# CAN-FD_Shield.net
KiCad netlist of a schematic drawn in EAGLE
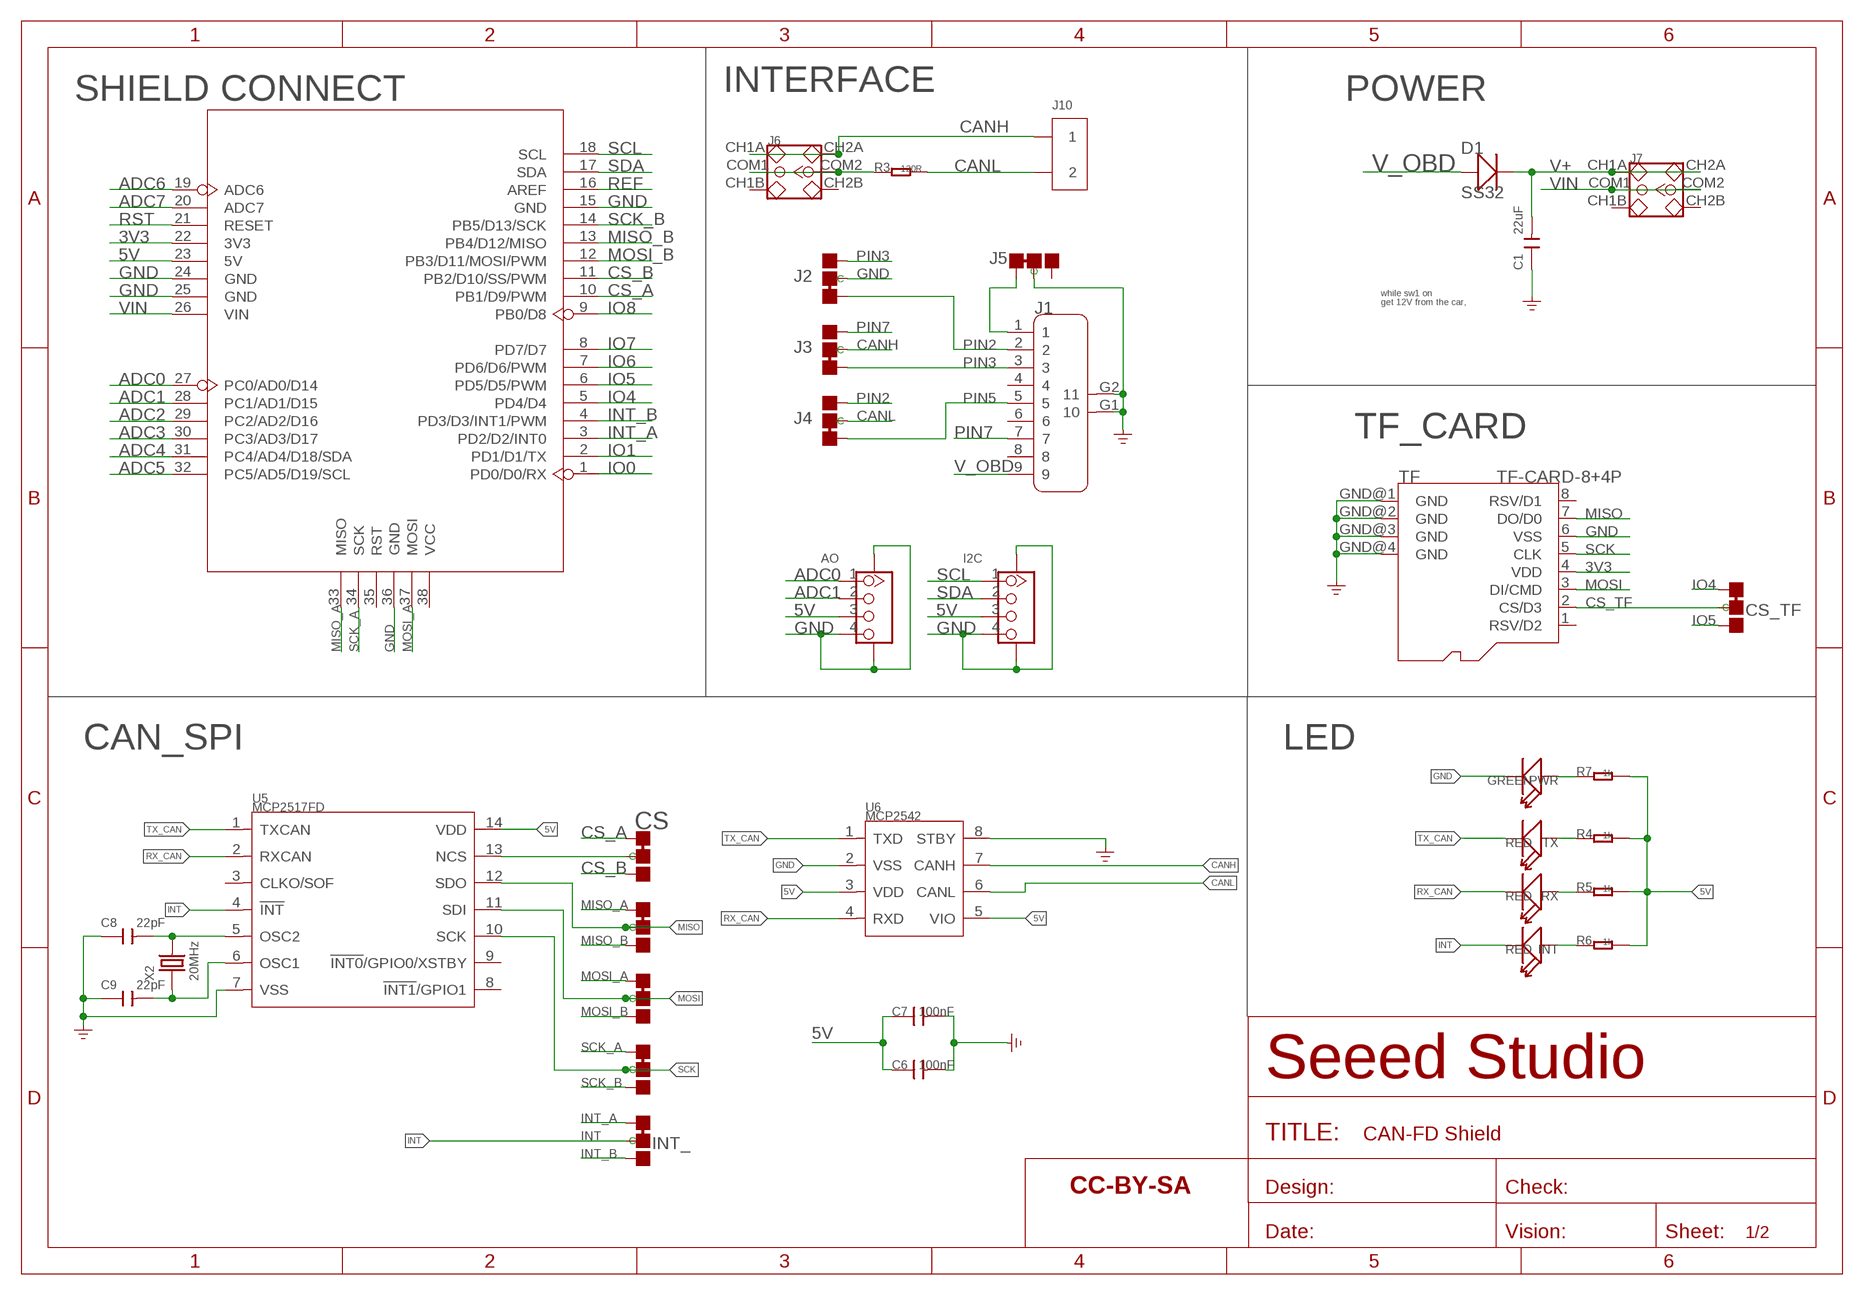
[diagram p0: schematic, sheet 1]

(export (version "E")
  (design (tool "Eeschema 10.0.6"))
  (components
    (comp (ref "AO")
      (value "GROVE-CONNECTOR-SMD'90D'")
      (footprint "eagle-import:HW4-SMD-2.0-90D")
      (libsource (lib "eagle-import") (part "GROVE-CONNECTOR-SMD'90D'"))
    )
    (comp (ref "C1")
      (value "22uF")
      (footprint "eagle-import:C1206")
      (libsource (lib "eagle-import") (part "CAP-1206"))
    )
    (comp (ref "C6")
      (value "100nF")
      (footprint "eagle-import:0603")
      (libsource (lib "eagle-import") (part "C-0603"))
    )
    (comp (ref "C7")
      (value "100nF")
      (footprint "eagle-import:0603")
      (libsource (lib "eagle-import") (part "C-0603"))
    )
    (comp (ref "C8")
      (value "22pF")
      (footprint "eagle-import:C0603")
      (libsource (lib "eagle-import") (part "CAP-0603"))
    )
    (comp (ref "C9")
      (value "22pF")
      (footprint "eagle-import:C0603")
      (libsource (lib "eagle-import") (part "CAP-0603"))
    )
    (comp (ref "CS")
      (value "JUMPER-3P-SHORT")
      (footprint "eagle-import:3P-SMD-SHORT")
      (libsource (lib "eagle-import") (part "JUMPER-3P-SHORT"))
    )
    (comp (ref "CS_TF")
      (value "JUMPER-3P-SHORT")
      (footprint "eagle-import:3P-SMD-SHORT")
      (libsource (lib "eagle-import") (part "JUMPER-3P-SHORT"))
    )
    (comp (ref "D1")
      (value "SS32")
      (footprint "eagle-import:D2010")
      (libsource (lib "eagle-import") (part "D-SMA"))
    )
    (comp (ref "I2C")
      (value "GROVE-CONNECTOR-SMD'90D'")
      (footprint "eagle-import:HW4-SMD-2.0-90D")
      (libsource (lib "eagle-import") (part "GROVE-CONNECTOR-SMD'90D'"))
    )
    (comp (ref "INT")
      (value "RED")
      (footprint "eagle-import:LED-0603")
      (libsource (lib "eagle-import") (part "LED'0603'"))
    )
    (comp (ref "INT_")
      (value "JUMPER-3P-SHORT")
      (footprint "eagle-import:3P-SMD-SHORT")
      (libsource (lib "eagle-import") (part "JUMPER-3P-SHORT"))
    )
    (comp (ref "J1")
      (value "DB9'MEAL'")
      (footprint "eagle-import:DB9-MEAL")
      (libsource (lib "eagle-import") (part "DB9'MEAL'"))
    )
    (comp (ref "J2")
      (value "JUMPER-3P-SHORT")
      (footprint "eagle-import:3P-SMD-SHORT")
      (libsource (lib "eagle-import") (part "JUMPER-3P-SHORT"))
    )
    (comp (ref "J3")
      (value "JUMPER-3P-SHORT")
      (footprint "eagle-import:3P-SMD-SHORT")
      (libsource (lib "eagle-import") (part "JUMPER-3P-SHORT"))
    )
    (comp (ref "J4")
      (value "JUMPER-3P-SHORT")
      (footprint "eagle-import:3P-SMD-SHORT")
      (libsource (lib "eagle-import") (part "JUMPER-3P-SHORT"))
    )
    (comp (ref "J5")
      (value "JUMPER-3P-SHORT")
      (footprint "eagle-import:3P-SMD-SHORT")
      (libsource (lib "eagle-import") (part "JUMPER-3P-SHORT"))
    )
    (comp (ref "J6")
      (value "SWITCH-2CH-6P")
      (footprint "eagle-import:6P-2CH-2.54-7.6X3.0")
      (libsource (lib "eagle-import") (part "SWITCH-2CH-6P"))
    )
    (comp (ref "J7")
      (value "SWITCH-2CH-6P")
      (footprint "eagle-import:6P-2CH-2.54-7.6X3.0")
      (libsource (lib "eagle-import") (part "SWITCH-2CH-6P"))
    )
    (comp (ref "J10")
      (value "SCREW-TERMINAL-2P'5.08'")
      (footprint "eagle-import:H2-5.0-10.5X8.0MM")
      (libsource (lib "eagle-import") (part "SCREW-TERMINAL-2P'5.08'"))
    )
    (comp (ref "MISO")
      (value "JUMPER-3P-SHORT")
      (footprint "eagle-import:3P-SMD-SHORT")
      (libsource (lib "eagle-import") (part "JUMPER-3P-SHORT"))
    )
    (comp (ref "MOSI")
      (value "JUMPER-3P-SHORT")
      (footprint "eagle-import:3P-SMD-SHORT")
      (libsource (lib "eagle-import") (part "JUMPER-3P-SHORT"))
    )
    (comp (ref "PWR")
      (value "GREEN")
      (footprint "eagle-import:LED-0603")
      (libsource (lib "eagle-import") (part "LED'0603'"))
    )
    (comp (ref "R3")
      (value "120R")
      (footprint "eagle-import:0603")
      (libsource (lib "eagle-import") (part "R-0603"))
    )
    (comp (ref "R4")
      (value "1k")
      (footprint "eagle-import:0603")
      (libsource (lib "eagle-import") (part "R-0603"))
    )
    (comp (ref "R5")
      (value "1k")
      (footprint "eagle-import:0603")
      (libsource (lib "eagle-import") (part "R-0603"))
    )
    (comp (ref "R6")
      (value "1k")
      (footprint "eagle-import:0603")
      (libsource (lib "eagle-import") (part "R-0603"))
    )
    (comp (ref "R7")
      (value "1k")
      (footprint "eagle-import:0603")
      (libsource (lib "eagle-import") (part "R-0603"))
    )
    (comp (ref "RX")
      (value "RED")
      (footprint "eagle-import:LED-0603")
      (libsource (lib "eagle-import") (part "LED'0603'"))
    )
    (comp (ref "SCK")
      (value "JUMPER-3P-SHORT")
      (footprint "eagle-import:3P-SMD-SHORT")
      (libsource (lib "eagle-import") (part "JUMPER-3P-SHORT"))
    )
    (comp (ref "TF")
      (value "TF-CARD-8+4P")
      (footprint "eagle-import:TF-8+4P-1.1-13.5X15MM")
      (libsource (lib "eagle-import") (part "TF-CARD-8+4P"))
    )
    (comp (ref "TX")
      (value "RED")
      (footprint "eagle-import:LED-0603")
      (libsource (lib "eagle-import") (part "LED'0603'"))
    )
    (comp (ref "U$5")
      (value "SEEEDSTUDIO-OPEN-SCH-FRAME")
      (footprint "eagle-import:SEEEDSTUDIO-PCB-FRAME")
      (libsource (lib "eagle-import") (part "SEEEDSTUDIO-OPEN-SCH-FRAME"))
    )
    (comp (ref "U4")
      (value "ARDUINO-38P'WITH/-SILK'")
      (footprint "eagle-import:ARDUINO-38P-WITH_-SILK-500519002")
      (libsource (lib "eagle-import") (part "ARDUINO-38P'WITH/-SILK'"))
    )
    (comp (ref "U5")
      (value "MCP2517FD")
      (footprint "eagle-import:SOIC14-1.27-8.6X3.9MM")
      (libsource (lib "eagle-import") (part "CONTROLLER-MCP2517FD"))
    )
    (comp (ref "U6")
      (value "MCP2542")
      (footprint "eagle-import:SOIC8-1.27-5X4MM")
      (libsource (lib "eagle-import") (part "TRANSCEIVER-MCP2542"))
    )
    (comp (ref "X2")
      (value "20MHz")
      (footprint "eagle-import:HC49US")
      (libsource (lib "eagle-import") (part "CRYSTAL-2P'HC49US'"))
    )
  )
  (nets
    (net (code "1") (name "3V3") (class "Default")
      (node (ref "TF") (pin "4") (pinfunction "VDD_4") (pintype "bidirectional"))
      (node (ref "U4") (pin "22") (pinfunction "3V3_22") (pintype "bidirectional"))
    )
    (net (code "2") (name "5V") (class "Default")
      (node (ref "AO") (pin "3") (pinfunction "3_3") (pintype "bidirectional"))
      (node (ref "C6") (pin "1") (pinfunction "1_1") (pintype "passive"))
      (node (ref "C7") (pin "1") (pinfunction "1_1") (pintype "passive"))
      (node (ref "I2C") (pin "3") (pinfunction "3_3") (pintype "bidirectional"))
      (node (ref "R4") (pin "2") (pinfunction "2_2") (pintype "passive"))
      (node (ref "R5") (pin "2") (pinfunction "2_2") (pintype "passive"))
      (node (ref "R6") (pin "2") (pinfunction "2_2") (pintype "passive"))
      (node (ref "R7") (pin "2") (pinfunction "2_2") (pintype "passive"))
      (node (ref "U4") (pin "23") (pinfunction "5V_23") (pintype "bidirectional"))
      (node (ref "U5") (pin "14") (pinfunction "VDD_14") (pintype "bidirectional"))
      (node (ref "U6") (pin "3") (pinfunction "VDD_3") (pintype "bidirectional"))
      (node (ref "U6") (pin "5") (pinfunction "VIO_5") (pintype "bidirectional"))
    )
    (net (code "3") (name "ADC0") (class "Default")
      (node (ref "AO") (pin "1") (pinfunction "1_1") (pintype "bidirectional"))
      (node (ref "U4") (pin "27") (pinfunction "PC0/AD0/D14_27") (pintype "bidirectional"))
    )
    (net (code "4") (name "ADC1") (class "Default")
      (node (ref "AO") (pin "2") (pinfunction "2_2") (pintype "bidirectional"))
      (node (ref "U4") (pin "28") (pinfunction "PC1/AD1/D15_28") (pintype "bidirectional"))
    )
    (net (code "5") (name "ADC2") (class "Default")
      (node (ref "U4") (pin "29") (pinfunction "PC2/AD2/D16_29") (pintype "bidirectional"))
    )
    (net (code "6") (name "ADC3") (class "Default")
      (node (ref "U4") (pin "30") (pinfunction "PC3/AD3/D17_30") (pintype "bidirectional"))
    )
    (net (code "7") (name "ADC4") (class "Default")
      (node (ref "U4") (pin "31") (pinfunction "PC4/AD4/D18/SDA_31") (pintype "bidirectional"))
    )
    (net (code "8") (name "ADC5") (class "Default")
      (node (ref "U4") (pin "32") (pinfunction "PC5/AD5/D19/SCL_32") (pintype "bidirectional"))
    )
    (net (code "9") (name "ADC6") (class "Default")
      (node (ref "U4") (pin "19") (pinfunction "ADC6_19") (pintype "bidirectional"))
    )
    (net (code "10") (name "ADC7") (class "Default")
      (node (ref "U4") (pin "20") (pinfunction "ADC7_20") (pintype "bidirectional"))
    )
    (net (code "11") (name "CANH") (class "Default")
      (node (ref "J10") (pin "1") (pinfunction "1_1") (pintype "bidirectional"))
      (node (ref "J3") (pin "MM") (pinfunction "C_MM") (pintype "bidirectional"))
      (node (ref "J6") (pin "CH1A") (pinfunction "CH1A_CH1A") (pintype "bidirectional"))
      (node (ref "J6") (pin "CH2A") (pinfunction "CH2A_CH2A") (pintype "bidirectional"))
      (node (ref "U6") (pin "7") (pinfunction "CANH_7") (pintype "bidirectional"))
    )
    (net (code "12") (name "CANL") (class "Default")
      (node (ref "J10") (pin "2") (pinfunction "2_2") (pintype "bidirectional"))
      (node (ref "J4") (pin "MM") (pinfunction "C_MM") (pintype "bidirectional"))
      (node (ref "R3") (pin "2") (pinfunction "2_2") (pintype "passive"))
      (node (ref "U6") (pin "6") (pinfunction "CANL_6") (pintype "bidirectional"))
    )
    (net (code "13") (name "CS_A") (class "Default")
      (node (ref "CS") (pin "11") (pinfunction "L_11") (pintype "bidirectional"))
      (node (ref "U4") (pin "10") (pinfunction "PB1/D9/PWM_10") (pintype "bidirectional"))
    )
    (net (code "14") (name "CS_B") (class "Default")
      (node (ref "CS") (pin "00") (pinfunction "R_00") (pintype "bidirectional"))
      (node (ref "U4") (pin "11") (pinfunction "PB2/D10/SS/PWM_11") (pintype "bidirectional"))
    )
    (net (code "15") (name "CS_TF") (class "Default")
      (node (ref "CS_TF") (pin "MM") (pinfunction "C_MM") (pintype "bidirectional"))
      (node (ref "TF") (pin "2") (pinfunction "CS/D3_2") (pintype "bidirectional"))
    )
    (net (code "16") (name "GND") (class "Default")
      (node (ref "AO") (pin "4") (pinfunction "4_4") (pintype "bidirectional"))
      (node (ref "AO") (pin "SS1") (pinfunction "SS1_SS1") (pintype "bidirectional"))
      (node (ref "AO") (pin "SS2") (pinfunction "SS2_SS2") (pintype "bidirectional"))
      (node (ref "C1") (pin "1") (pinfunction "1_1") (pintype "passive"))
      (node (ref "C6") (pin "2") (pinfunction "2_2") (pintype "passive"))
      (node (ref "C7") (pin "2") (pinfunction "2_2") (pintype "passive"))
      (node (ref "C8") (pin "1") (pinfunction "1_1") (pintype "passive"))
      (node (ref "C9") (pin "1") (pinfunction "1_1") (pintype "passive"))
      (node (ref "I2C") (pin "4") (pinfunction "4_4") (pintype "bidirectional"))
      (node (ref "I2C") (pin "SS1") (pinfunction "SS1_SS1") (pintype "bidirectional"))
      (node (ref "I2C") (pin "SS2") (pinfunction "SS2_SS2") (pintype "bidirectional"))
      (node (ref "J1") (pin "G1") (pinfunction "10_G1") (pintype "bidirectional"))
      (node (ref "J1") (pin "G2") (pinfunction "11_G2") (pintype "bidirectional"))
      (node (ref "J2") (pin "MM") (pinfunction "C_MM") (pintype "bidirectional"))
      (node (ref "J5") (pin "MM") (pinfunction "C_MM") (pintype "bidirectional"))
      (node (ref "PWR") (pin "-") (pinfunction "-_-") (pintype "passive"))
      (node (ref "TF") (pin "6") (pinfunction "VSS_6") (pintype "bidirectional"))
      (node (ref "TF") (pin "GND@1") (pinfunction "GND_GND@1") (pintype "bidirectional"))
      (node (ref "TF") (pin "GND@2") (pinfunction "GND_GND@2") (pintype "bidirectional"))
      (node (ref "TF") (pin "GND@3") (pinfunction "GND_GND@3") (pintype "bidirectional"))
      (node (ref "TF") (pin "GND@4") (pinfunction "GND_GND@4") (pintype "bidirectional"))
      (node (ref "U4") (pin "15") (pinfunction "GND_15") (pintype "bidirectional"))
      (node (ref "U4") (pin "24") (pinfunction "GND_24") (pintype "bidirectional"))
      (node (ref "U4") (pin "25") (pinfunction "GND_25") (pintype "bidirectional"))
      (node (ref "U4") (pin "36") (pinfunction "GND_36") (pintype "bidirectional"))
      (node (ref "U5") (pin "7") (pinfunction "VSS_7") (pintype "bidirectional"))
      (node (ref "U6") (pin "2") (pinfunction "VSS_2") (pintype "bidirectional"))
      (node (ref "U6") (pin "8") (pinfunction "STBY_8") (pintype "bidirectional"))
    )
    (net (code "17") (name "INT") (class "Default")
      (node (ref "INT") (pin "-") (pinfunction "-_-") (pintype "passive"))
      (node (ref "INT_") (pin "MM") (pinfunction "C_MM") (pintype "bidirectional"))
      (node (ref "U5") (pin "4") (pinfunction "~{INT}_4") (pintype "bidirectional"))
    )
    (net (code "18") (name "INT_A") (class "Default")
      (node (ref "INT_") (pin "11") (pinfunction "L_11") (pintype "bidirectional"))
      (node (ref "U4") (pin "3") (pinfunction "PD2/D2/INT0_3") (pintype "bidirectional"))
    )
    (net (code "19") (name "INT_B") (class "Default")
      (node (ref "INT_") (pin "00") (pinfunction "R_00") (pintype "bidirectional"))
      (node (ref "U4") (pin "4") (pinfunction "PD3/D3/INT1/PWM_4") (pintype "bidirectional"))
    )
    (net (code "20") (name "IO0") (class "Default")
      (node (ref "U4") (pin "1") (pinfunction "PD0/D0/RX_1") (pintype "bidirectional"))
    )
    (net (code "21") (name "IO1") (class "Default")
      (node (ref "U4") (pin "2") (pinfunction "PD1/D1/TX_2") (pintype "bidirectional"))
    )
    (net (code "22") (name "IO4") (class "Default")
      (node (ref "CS_TF") (pin "11") (pinfunction "L_11") (pintype "bidirectional"))
      (node (ref "U4") (pin "5") (pinfunction "PD4/D4_5") (pintype "bidirectional"))
    )
    (net (code "23") (name "IO5") (class "Default")
      (node (ref "CS_TF") (pin "00") (pinfunction "R_00") (pintype "bidirectional"))
      (node (ref "U4") (pin "6") (pinfunction "PD5/D5/PWM_6") (pintype "bidirectional"))
    )
    (net (code "24") (name "IO6") (class "Default")
      (node (ref "U4") (pin "7") (pinfunction "PD6/D6/PWM_7") (pintype "bidirectional"))
    )
    (net (code "25") (name "IO7") (class "Default")
      (node (ref "U4") (pin "8") (pinfunction "PD7/D7_8") (pintype "bidirectional"))
    )
    (net (code "26") (name "IO8") (class "Default")
      (node (ref "U4") (pin "9") (pinfunction "PB0/D8_9") (pintype "bidirectional"))
    )
    (net (code "27") (name "MISO") (class "Default")
      (node (ref "MISO") (pin "MM") (pinfunction "C_MM") (pintype "bidirectional"))
      (node (ref "TF") (pin "7") (pinfunction "DO/D0_7") (pintype "bidirectional"))
      (node (ref "U5") (pin "12") (pinfunction "SDO_12") (pintype "bidirectional"))
    )
    (net (code "28") (name "MISO_A") (class "Default")
      (node (ref "MISO") (pin "11") (pinfunction "L_11") (pintype "bidirectional"))
      (node (ref "U4") (pin "33") (pinfunction "MISO_33") (pintype "bidirectional"))
    )
    (net (code "29") (name "MISO_B") (class "Default")
      (node (ref "MISO") (pin "00") (pinfunction "R_00") (pintype "bidirectional"))
      (node (ref "U4") (pin "13") (pinfunction "PB4/D12/MISO_13") (pintype "bidirectional"))
    )
    (net (code "30") (name "MOSI") (class "Default")
      (node (ref "MOSI") (pin "MM") (pinfunction "C_MM") (pintype "bidirectional"))
      (node (ref "TF") (pin "3") (pinfunction "DI/CMD_3") (pintype "bidirectional"))
      (node (ref "U5") (pin "11") (pinfunction "SDI_11") (pintype "bidirectional"))
    )
    (net (code "31") (name "MOSI_A") (class "Default")
      (node (ref "MOSI") (pin "11") (pinfunction "L_11") (pintype "bidirectional"))
      (node (ref "U4") (pin "37") (pinfunction "MOSI_37") (pintype "bidirectional"))
    )
    (net (code "32") (name "MOSI_B") (class "Default")
      (node (ref "MOSI") (pin "00") (pinfunction "R_00") (pintype "bidirectional"))
      (node (ref "U4") (pin "12") (pinfunction "PB3/D11/MOSI/PWM_12") (pintype "bidirectional"))
    )
    (net (code "33") (name "Net-(CS-C)") (class "Default")
      (node (ref "CS") (pin "MM") (pinfunction "C_MM") (pintype "bidirectional"))
      (node (ref "U5") (pin "13") (pinfunction "NCS_13") (pintype "bidirectional"))
    )
    (net (code "34") (name "Net-(INT-Pad+)") (class "Default")
      (node (ref "INT") (pin "+") (pinfunction "+_+") (pintype "passive"))
      (node (ref "R6") (pin "1") (pinfunction "1_1") (pintype "passive"))
    )
    (net (code "35") (name "Net-(J5-L)") (class "Default")
      (node (ref "J1") (pin "1") (pinfunction "1_1") (pintype "bidirectional"))
      (node (ref "J5") (pin "11") (pinfunction "L_11") (pintype "bidirectional"))
    )
    (net (code "36") (name "Net-(J6-PadCOM1)") (class "Default")
      (node (ref "J6") (pin "COM1") (pinfunction "COM1_COM1") (pintype "bidirectional"))
      (node (ref "J6") (pin "COM2") (pinfunction "COM2_COM2") (pintype "bidirectional"))
      (node (ref "R3") (pin "1") (pinfunction "1_1") (pintype "passive"))
    )
    (net (code "37") (name "Net-(PWR-Pad+)") (class "Default")
      (node (ref "PWR") (pin "+") (pinfunction "+_+") (pintype "passive"))
      (node (ref "R7") (pin "1") (pinfunction "1_1") (pintype "passive"))
    )
    (net (code "38") (name "Net-(R4-Pad1)") (class "Default")
      (node (ref "R4") (pin "1") (pinfunction "1_1") (pintype "passive"))
      (node (ref "TX") (pin "+") (pinfunction "+_+") (pintype "passive"))
    )
    (net (code "39") (name "Net-(R5-Pad1)") (class "Default")
      (node (ref "R5") (pin "1") (pinfunction "1_1") (pintype "passive"))
      (node (ref "RX") (pin "+") (pinfunction "+_+") (pintype "passive"))
    )
    (net (code "40") (name "Net-(U5-OSC1)") (class "Default")
      (node (ref "C9") (pin "2") (pinfunction "2_2") (pintype "passive"))
      (node (ref "U5") (pin "6") (pinfunction "OSC1_6") (pintype "bidirectional"))
      (node (ref "X2") (pin "1") (pinfunction "1_1") (pintype "passive"))
    )
    (net (code "41") (name "Net-(U5-OSC2)") (class "Default")
      (node (ref "C8") (pin "2") (pinfunction "2_2") (pintype "passive"))
      (node (ref "U5") (pin "5") (pinfunction "OSC2_5") (pintype "bidirectional"))
      (node (ref "X2") (pin "2") (pinfunction "2_2") (pintype "passive"))
    )
    (net (code "42") (name "PIN2") (class "Default")
      (node (ref "J1") (pin "2") (pinfunction "2_2") (pintype "bidirectional"))
      (node (ref "J2") (pin "11") (pinfunction "L_11") (pintype "bidirectional"))
      (node (ref "J4") (pin "00") (pinfunction "R_00") (pintype "bidirectional"))
    )
    (net (code "43") (name "PIN3") (class "Default")
      (node (ref "J1") (pin "3") (pinfunction "3_3") (pintype "bidirectional"))
      (node (ref "J2") (pin "00") (pinfunction "R_00") (pintype "bidirectional"))
      (node (ref "J3") (pin "11") (pinfunction "L_11") (pintype "bidirectional"))
    )
    (net (code "44") (name "PIN5") (class "Default")
      (node (ref "J1") (pin "5") (pinfunction "5_5") (pintype "bidirectional"))
      (node (ref "J4") (pin "11") (pinfunction "L_11") (pintype "bidirectional"))
    )
    (net (code "45") (name "PIN7") (class "Default")
      (node (ref "J1") (pin "7") (pinfunction "7_7") (pintype "bidirectional"))
      (node (ref "J3") (pin "00") (pinfunction "R_00") (pintype "bidirectional"))
    )
    (net (code "46") (name "REF") (class "Default")
      (node (ref "U4") (pin "16") (pinfunction "AREF_16") (pintype "bidirectional"))
    )
    (net (code "47") (name "RST") (class "Default")
      (node (ref "U4") (pin "21") (pinfunction "RESET_21") (pintype "bidirectional"))
    )
    (net (code "48") (name "RX_CAN") (class "Default")
      (node (ref "RX") (pin "-") (pinfunction "-_-") (pintype "passive"))
      (node (ref "U5") (pin "2") (pinfunction "RXCAN_2") (pintype "bidirectional"))
      (node (ref "U6") (pin "4") (pinfunction "RXD_4") (pintype "bidirectional"))
    )
    (net (code "49") (name "SCK") (class "Default")
      (node (ref "SCK") (pin "MM") (pinfunction "C_MM") (pintype "bidirectional"))
      (node (ref "TF") (pin "5") (pinfunction "CLK_5") (pintype "bidirectional"))
      (node (ref "U5") (pin "10") (pinfunction "SCK_10") (pintype "bidirectional"))
    )
    (net (code "50") (name "SCK_A") (class "Default")
      (node (ref "SCK") (pin "11") (pinfunction "L_11") (pintype "bidirectional"))
      (node (ref "U4") (pin "34") (pinfunction "SCK_34") (pintype "bidirectional"))
    )
    (net (code "51") (name "SCK_B") (class "Default")
      (node (ref "SCK") (pin "00") (pinfunction "R_00") (pintype "bidirectional"))
      (node (ref "U4") (pin "14") (pinfunction "PB5/D13/SCK_14") (pintype "bidirectional"))
    )
    (net (code "52") (name "SCL") (class "Default")
      (node (ref "I2C") (pin "1") (pinfunction "1_1") (pintype "bidirectional"))
      (node (ref "U4") (pin "18") (pinfunction "SCL_18") (pintype "bidirectional"))
    )
    (net (code "53") (name "SDA") (class "Default")
      (node (ref "I2C") (pin "2") (pinfunction "2_2") (pintype "bidirectional"))
      (node (ref "U4") (pin "17") (pinfunction "SDA_17") (pintype "bidirectional"))
    )
    (net (code "54") (name "TX_CAN") (class "Default")
      (node (ref "TX") (pin "-") (pinfunction "-_-") (pintype "passive"))
      (node (ref "U5") (pin "1") (pinfunction "TXCAN_1") (pintype "bidirectional"))
      (node (ref "U6") (pin "1") (pinfunction "TXD_1") (pintype "bidirectional"))
    )
    (net (code "55") (name "V+") (class "Default")
      (node (ref "C1") (pin "2") (pinfunction "2_2") (pintype "passive"))
      (node (ref "D1") (pin "-") (pinfunction "-_-") (pintype "passive"))
      (node (ref "J7") (pin "CH1A") (pinfunction "CH1A_CH1A") (pintype "bidirectional"))
      (node (ref "J7") (pin "CH2A") (pinfunction "CH2A_CH2A") (pintype "bidirectional"))
    )
    (net (code "56") (name "VIN") (class "Default")
      (node (ref "J7") (pin "COM1") (pinfunction "COM1_COM1") (pintype "bidirectional"))
      (node (ref "J7") (pin "COM2") (pinfunction "COM2_COM2") (pintype "bidirectional"))
      (node (ref "U4") (pin "26") (pinfunction "VIN_26") (pintype "bidirectional"))
    )
    (net (code "57") (name "V_OBD") (class "Default")
      (node (ref "D1") (pin "+") (pinfunction "+_+") (pintype "passive"))
      (node (ref "J1") (pin "9") (pinfunction "9_9") (pintype "bidirectional"))
    )
    (net (code "58") (name "unconnected-(J1-Pad4)") (class "Default")
      (node (ref "J1") (pin "4") (pinfunction "4_4") (pintype "bidirectional"))
    )
    (net (code "59") (name "unconnected-(J1-Pad6)") (class "Default")
      (node (ref "J1") (pin "6") (pinfunction "6_6") (pintype "bidirectional"))
    )
    (net (code "60") (name "unconnected-(J1-Pad8)") (class "Default")
      (node (ref "J1") (pin "8") (pinfunction "8_8") (pintype "bidirectional"))
    )
    (net (code "61") (name "unconnected-(J5-R-Pad00)") (class "Default")
      (node (ref "J5") (pin "00") (pinfunction "R_00") (pintype "bidirectional"))
    )
    (net (code "62") (name "unconnected-(J6-PadCH1B)") (class "Default")
      (node (ref "J6") (pin "CH1B") (pinfunction "CH1B_CH1B") (pintype "bidirectional"))
    )
    (net (code "63") (name "unconnected-(J6-PadCH2B)") (class "Default")
      (node (ref "J6") (pin "CH2B") (pinfunction "CH2B_CH2B") (pintype "bidirectional"))
    )
    (net (code "64") (name "unconnected-(J7-PadCH1B)") (class "Default")
      (node (ref "J7") (pin "CH1B") (pinfunction "CH1B_CH1B") (pintype "bidirectional"))
    )
    (net (code "65") (name "unconnected-(J7-PadCH2B)") (class "Default")
      (node (ref "J7") (pin "CH2B") (pinfunction "CH2B_CH2B") (pintype "bidirectional"))
    )
    (net (code "66") (name "unconnected-(TF-RSV{slash}D1-Pad8)") (class "Default")
      (node (ref "TF") (pin "8") (pinfunction "RSV/D1_8") (pintype "bidirectional"))
    )
    (net (code "67") (name "unconnected-(TF-RSV{slash}D2-Pad1)") (class "Default")
      (node (ref "TF") (pin "1") (pinfunction "RSV/D2_1") (pintype "bidirectional"))
    )
    (net (code "68") (name "unconnected-(U4-RST-Pad35)") (class "Default")
      (node (ref "U4") (pin "35") (pinfunction "RST_35") (pintype "bidirectional"))
    )
    (net (code "69") (name "unconnected-(U4-VCC-Pad38)") (class "Default")
      (node (ref "U4") (pin "38") (pinfunction "VCC_38") (pintype "bidirectional"))
    )
    (net (code "70") (name "unconnected-(U5-CLKO{slash}SOF-Pad3)") (class "Default")
      (node (ref "U5") (pin "3") (pinfunction "CLKO/SOF_3") (pintype "bidirectional"))
    )
    (net (code "71") (name "unconnected-(U5-~{INT0}{slash}GPIO0{slash}XSTBY-Pad9)") (class "Default")
      (node (ref "U5") (pin "9") (pinfunction "~{INT0}/GPIO0/XSTBY_9") (pintype "bidirectional"))
    )
    (net (code "72") (name "unconnected-(U5-~{INT1}{slash}GPIO1-Pad8)") (class "Default")
      (node (ref "U5") (pin "8") (pinfunction "~{INT1}/GPIO1_8") (pintype "bidirectional"))
    )
  )
)
